# hand_fpc.net
KiCad netlist of a schematic drawn in Altium Designer
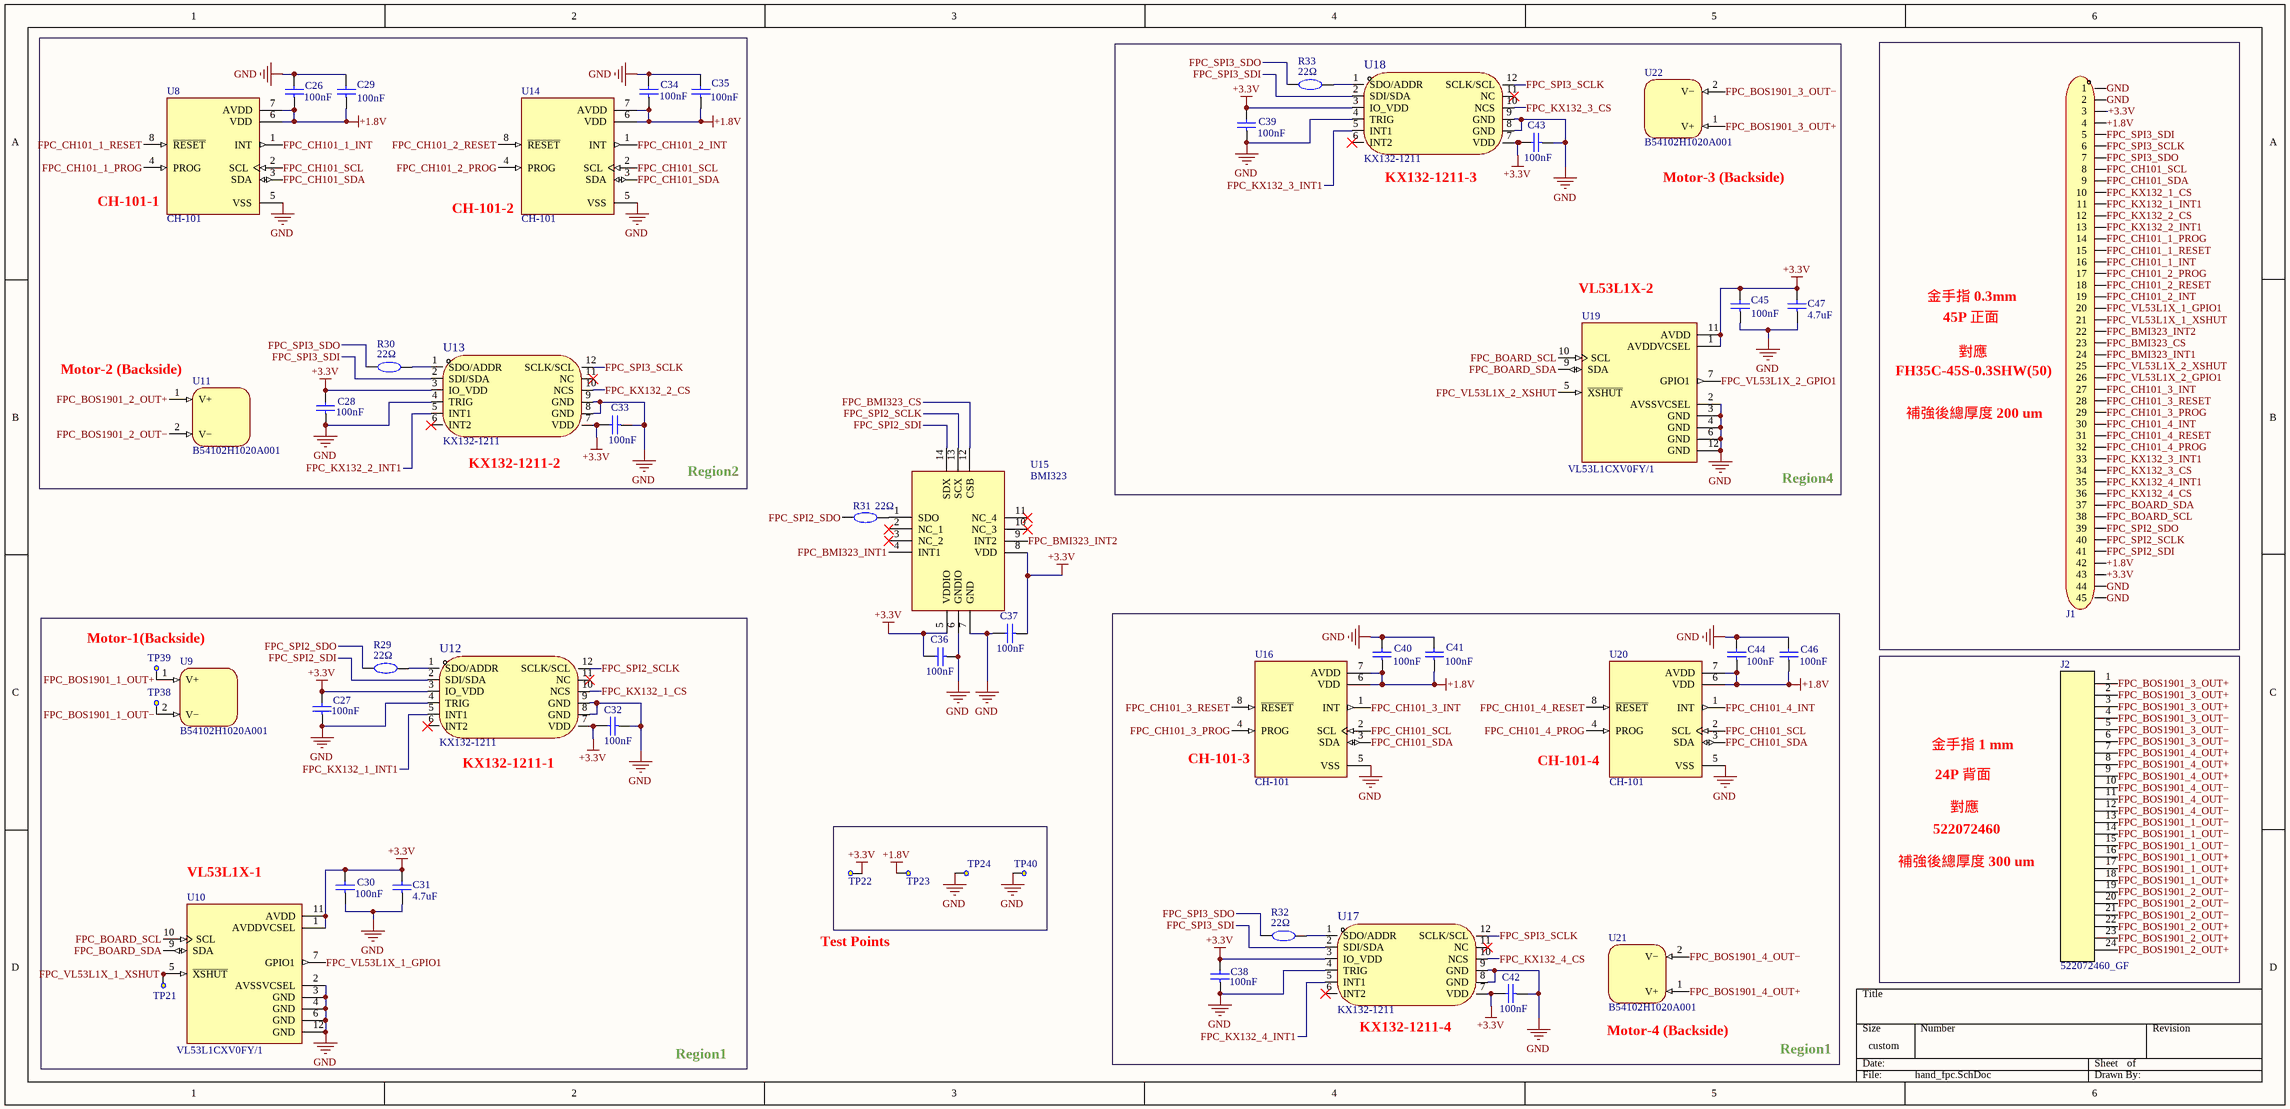
[diagram p0: hand_fpc.SchDoc]

(export (version "E")
  (design (tool "Eeschema 10.0.6"))
  (components
    (comp (ref "C26")
      (value "100nF")
      (footprint "C1206_FPC")
      (description "MLCC, 100 nF, 50 V, ± 10%, X7R, 1206")
      (fields
        (field (name "MANUFACTURER") "SAMSUNG(三星)")
        (field (name "MANUFACTURER PART") "CL31B104KBCNNNC")
      )
      (libsource (lib "hand_ad_lib") (part "CL31B104KBCNNNC"))
    )
    (comp (ref "C27")
      (value "100nF")
      (footprint "C1206_FPC")
      (description "MLCC, 100 nF, 50 V, ± 10%, X7R, 1206")
      (fields
        (field (name "MANUFACTURER") "SAMSUNG(三星)")
        (field (name "MANUFACTURER PART") "CL31B104KBCNNNC")
      )
      (libsource (lib "hand_ad_lib") (part "CL31B104KBCNNNC"))
    )
    (comp (ref "C28")
      (value "100nF")
      (footprint "C1206_FPC")
      (description "MLCC, 100 nF, 50 V, ± 10%, X7R, 1206")
      (fields
        (field (name "MANUFACTURER") "SAMSUNG(三星)")
        (field (name "MANUFACTURER PART") "CL31B104KBCNNNC")
      )
      (libsource (lib "hand_ad_lib") (part "CL31B104KBCNNNC"))
    )
    (comp (ref "C29")
      (value "100nF")
      (footprint "C1206_FPC")
      (description "MLCC, 100 nF, 50 V, ± 10%, X7R, 1206")
      (fields
        (field (name "MANUFACTURER") "SAMSUNG(三星)")
        (field (name "MANUFACTURER PART") "CL31B104KBCNNNC")
      )
      (libsource (lib "hand_ad_lib") (part "CL31B104KBCNNNC"))
    )
    (comp (ref "C30")
      (value "100nF")
      (footprint "C1206_FPC")
      (description "MLCC, 100 nF, 50 V, ± 10%, X7R, 1206")
      (fields
        (field (name "MANUFACTURER") "SAMSUNG(三星)")
        (field (name "MANUFACTURER PART") "CL31B104KBCNNNC")
      )
      (libsource (lib "hand_ad_lib") (part "CL31B104KBCNNNC"))
    )
    (comp (ref "C31")
      (value "4.7uF")
      (footprint "C1206_FPC")
      (description "MLCC, 4.7 uF, 50 V, ± 10%, X7R, 1206")
      (fields (field (name "TOLERANCE") "±10%") (field (name "MANUFACTURER") "FH(风华)"))
      (libsource (lib "hand_ad_lib") (part "1206B475K500NT"))
    )
    (comp (ref "C32")
      (value "100nF")
      (footprint "C1206_FPC")
      (description "MLCC, 100 nF, 50 V, ± 10%, X7R, 1206")
      (fields
        (field (name "MANUFACTURER") "SAMSUNG(三星)")
        (field (name "MANUFACTURER PART") "CL31B104KBCNNNC")
      )
      (libsource (lib "hand_ad_lib") (part "CL31B104KBCNNNC"))
    )
    (comp (ref "C33")
      (value "100nF")
      (footprint "C1206_FPC")
      (description "MLCC, 100 nF, 50 V, ± 10%, X7R, 1206")
      (fields
        (field (name "MANUFACTURER") "SAMSUNG(三星)")
        (field (name "MANUFACTURER PART") "CL31B104KBCNNNC")
      )
      (libsource (lib "hand_ad_lib") (part "CL31B104KBCNNNC"))
    )
    (comp (ref "C34")
      (value "100nF")
      (footprint "C1206_FPC")
      (description "MLCC, 100 nF, 50 V, ± 10%, X7R, 1206")
      (fields
        (field (name "MANUFACTURER") "SAMSUNG(三星)")
        (field (name "MANUFACTURER PART") "CL31B104KBCNNNC")
      )
      (libsource (lib "hand_ad_lib") (part "CL31B104KBCNNNC"))
    )
    (comp (ref "C35")
      (value "100nF")
      (footprint "C1206_FPC")
      (description "MLCC, 100 nF, 50 V, ± 10%, X7R, 1206")
      (fields
        (field (name "MANUFACTURER") "SAMSUNG(三星)")
        (field (name "MANUFACTURER PART") "CL31B104KBCNNNC")
      )
      (libsource (lib "hand_ad_lib") (part "CL31B104KBCNNNC"))
    )
    (comp (ref "C36")
      (value "100nF")
      (footprint "C1206_FPC")
      (description "MLCC, 100 nF, 50 V, ± 10%, X7R, 1206")
      (fields
        (field (name "MANUFACTURER") "SAMSUNG(三星)")
        (field (name "MANUFACTURER PART") "CL31B104KBCNNNC")
      )
      (libsource (lib "hand_ad_lib") (part "CL31B104KBCNNNC"))
    )
    (comp (ref "C37")
      (value "100nF")
      (footprint "C1206_FPC")
      (description "MLCC, 100 nF, 50 V, ± 10%, X7R, 1206")
      (fields
        (field (name "MANUFACTURER") "SAMSUNG(三星)")
        (field (name "MANUFACTURER PART") "CL31B104KBCNNNC")
      )
      (libsource (lib "hand_ad_lib") (part "CL31B104KBCNNNC"))
    )
    (comp (ref "C38")
      (value "100nF")
      (footprint "C1206_FPC")
      (description "MLCC, 100 nF, 50 V, ± 10%, X7R, 1206")
      (fields
        (field (name "MANUFACTURER") "SAMSUNG(三星)")
        (field (name "MANUFACTURER PART") "CL31B104KBCNNNC")
      )
      (libsource (lib "hand_ad_lib") (part "CL31B104KBCNNNC"))
    )
    (comp (ref "C39")
      (value "100nF")
      (footprint "C1206_FPC")
      (description "MLCC, 100 nF, 50 V, ± 10%, X7R, 1206")
      (fields
        (field (name "MANUFACTURER") "SAMSUNG(三星)")
        (field (name "MANUFACTURER PART") "CL31B104KBCNNNC")
      )
      (libsource (lib "hand_ad_lib") (part "CL31B104KBCNNNC"))
    )
    (comp (ref "C40")
      (value "100nF")
      (footprint "C1206_FPC")
      (description "MLCC, 100 nF, 50 V, ± 10%, X7R, 1206")
      (fields
        (field (name "MANUFACTURER") "SAMSUNG(三星)")
        (field (name "MANUFACTURER PART") "CL31B104KBCNNNC")
      )
      (libsource (lib "hand_ad_lib") (part "CL31B104KBCNNNC"))
    )
    (comp (ref "C41")
      (value "100nF")
      (footprint "C1206_FPC")
      (description "MLCC, 100 nF, 50 V, ± 10%, X7R, 1206")
      (fields
        (field (name "MANUFACTURER") "SAMSUNG(三星)")
        (field (name "MANUFACTURER PART") "CL31B104KBCNNNC")
      )
      (libsource (lib "hand_ad_lib") (part "CL31B104KBCNNNC"))
    )
    (comp (ref "C42")
      (value "100nF")
      (footprint "C1206_FPC")
      (description "MLCC, 100 nF, 50 V, ± 10%, X7R, 1206")
      (fields
        (field (name "MANUFACTURER") "SAMSUNG(三星)")
        (field (name "MANUFACTURER PART") "CL31B104KBCNNNC")
      )
      (libsource (lib "hand_ad_lib") (part "CL31B104KBCNNNC"))
    )
    (comp (ref "C43")
      (value "100nF")
      (footprint "C1206_FPC")
      (description "MLCC, 100 nF, 50 V, ± 10%, X7R, 1206")
      (fields
        (field (name "MANUFACTURER") "SAMSUNG(三星)")
        (field (name "MANUFACTURER PART") "CL31B104KBCNNNC")
      )
      (libsource (lib "hand_ad_lib") (part "CL31B104KBCNNNC"))
    )
    (comp (ref "C44")
      (value "100nF")
      (footprint "C1206_FPC")
      (description "MLCC, 100 nF, 50 V, ± 10%, X7R, 1206")
      (fields
        (field (name "MANUFACTURER") "SAMSUNG(三星)")
        (field (name "MANUFACTURER PART") "CL31B104KBCNNNC")
      )
      (libsource (lib "hand_ad_lib") (part "CL31B104KBCNNNC"))
    )
    (comp (ref "C45")
      (value "100nF")
      (footprint "C1206_FPC")
      (description "MLCC, 100 nF, 50 V, ± 10%, X7R, 1206")
      (fields
        (field (name "MANUFACTURER") "SAMSUNG(三星)")
        (field (name "MANUFACTURER PART") "CL31B104KBCNNNC")
      )
      (libsource (lib "hand_ad_lib") (part "CL31B104KBCNNNC"))
    )
    (comp (ref "C46")
      (value "100nF")
      (footprint "C1206_FPC")
      (description "MLCC, 100 nF, 50 V, ± 10%, X7R, 1206")
      (fields
        (field (name "MANUFACTURER") "SAMSUNG(三星)")
        (field (name "MANUFACTURER PART") "CL31B104KBCNNNC")
      )
      (libsource (lib "hand_ad_lib") (part "CL31B104KBCNNNC"))
    )
    (comp (ref "C47")
      (value "4.7uF")
      (footprint "C1206_FPC")
      (description "MLCC, 4.7 uF, 50 V, ± 10%, X7R, 1206")
      (fields (field (name "TOLERANCE") "±10%") (field (name "MANUFACTURER") "FH(风华)"))
      (libsource (lib "hand_ad_lib") (part "1206B475K500NT"))
    )
    (comp (ref "J1")
      (value "FH35C-45S-0.3SHW-GF")
      (footprint "FH35C-45S-0.3SHW-GF-REVERSE")
      (description "Golden Finger Footprint of FH35C-45S-0.3SHW, 45 Pins, 0.3mm cross, up contact")
      (libsource (lib "hand_ad_lib") (part "FH35C-45S-0.3SHW-GF"))
    )
    (comp (ref "J2")
      (value "522072460_GF")
      (footprint "522072460-GF-Back")
      (description "FFC 1mm 24P Golden Finger")
      (libsource (lib "hand_ad_lib") (part "522072460_GF"))
    )
    (comp (ref "R29")
      (value "22Ω")
      (footprint "R1206_FPC")
      (description "Resistor, Res Thick Film 1206 22 Ohm 1% 0.25W(1/4W) ±100ppm/°C Pad SMD T/R 200 V")
      (fields
        (field (name "MANUFACTURER") "UNI-ROYAL(厚声)")
        (field (name "MANUFACTURER PART") "1206W4F220JT5E")
        (field (name "NAME") "22Ω")
      )
      (libsource (lib "hand_ad_lib") (part "1206W4F220JT5E"))
    )
    (comp (ref "R30")
      (value "22Ω")
      (footprint "R1206_FPC")
      (description "Resistor, Res Thick Film 1206 22 Ohm 1% 0.25W(1/4W) ±100ppm/°C Pad SMD T/R 200 V")
      (fields
        (field (name "MANUFACTURER") "UNI-ROYAL(厚声)")
        (field (name "MANUFACTURER PART") "1206W4F220JT5E")
        (field (name "NAME") "22Ω")
      )
      (libsource (lib "hand_ad_lib") (part "1206W4F220JT5E"))
    )
    (comp (ref "R31")
      (value "22Ω")
      (footprint "R1206_FPC")
      (description "Resistor, Res Thick Film 1206 22 Ohm 1% 0.25W(1/4W) ±100ppm/°C Pad SMD T/R 200 V")
      (fields
        (field (name "MANUFACTURER") "UNI-ROYAL(厚声)")
        (field (name "MANUFACTURER PART") "1206W4F220JT5E")
        (field (name "NAME") "22Ω")
      )
      (libsource (lib "hand_ad_lib") (part "1206W4F220JT5E"))
    )
    (comp (ref "R32")
      (value "22Ω")
      (footprint "R1206_FPC")
      (description "Resistor, Res Thick Film 1206 22 Ohm 1% 0.25W(1/4W) ±100ppm/°C Pad SMD T/R 200 V")
      (fields
        (field (name "MANUFACTURER") "UNI-ROYAL(厚声)")
        (field (name "MANUFACTURER PART") "1206W4F220JT5E")
        (field (name "NAME") "22Ω")
      )
      (libsource (lib "hand_ad_lib") (part "1206W4F220JT5E"))
    )
    (comp (ref "R33")
      (value "22Ω")
      (footprint "R1206_FPC")
      (description "Resistor, Res Thick Film 1206 22 Ohm 1% 0.25W(1/4W) ±100ppm/°C Pad SMD T/R 200 V")
      (fields
        (field (name "MANUFACTURER") "UNI-ROYAL(厚声)")
        (field (name "MANUFACTURER PART") "1206W4F220JT5E")
        (field (name "NAME") "22Ω")
      )
      (libsource (lib "hand_ad_lib") (part "1206W4F220JT5E"))
    )
    (comp (ref "TP21")
      (value "Test point")
      (footprint "Test_Point_FPC")
      (libsource (lib "hand_ad_lib") (part "Test_Point"))
    )
    (comp (ref "TP22")
      (value "Test point")
      (footprint "Test_Point_FPC")
      (libsource (lib "hand_ad_lib") (part "Test_Point"))
    )
    (comp (ref "TP23")
      (value "Test point")
      (footprint "Test_Point_FPC")
      (libsource (lib "hand_ad_lib") (part "Test_Point"))
    )
    (comp (ref "TP24")
      (value "Test point")
      (footprint "Test_Point_FPC")
      (libsource (lib "hand_ad_lib") (part "Test_Point"))
    )
    (comp (ref "TP38")
      (value "Test point")
      (footprint "Test_Point_FPC")
      (libsource (lib "hand_ad_lib") (part "Test_Point"))
    )
    (comp (ref "TP39")
      (value "Test point")
      (footprint "Test_Point_FPC")
      (libsource (lib "hand_ad_lib") (part "Test_Point"))
    )
    (comp (ref "TP40")
      (value "Test point")
      (footprint "Test_Point_FPC")
      (libsource (lib "hand_ad_lib") (part "Test_Point"))
    )
    (comp (ref "U8")
      (value "CH-101")
      (footprint "XDCR_CH-101")
      (description "Ultrasonic MEMS based Time-of-Flight _ToF_ Range Sensor")
      (fields (field (name "MF") "TDK InvenSense"))
      (libsource (lib "hand_ad_lib") (part "CH-101"))
    )
    (comp (ref "U9")
      (value "B54102H1020A001")
      (footprint "B54102H1020A001")
      (description "TDK PowerHap™, Piezo Haptic Actuator Metal Sealed 15N 65um 32KHz Bulk")
      (fields (field (name "MANUFACTURER") "TDK EPCOS") (field (name "NAME") "B54102H1020A001"))
      (libsource (lib "hand_ad_lib") (part "B54102H1020A001"))
    )
    (comp (ref "U10")
      (value "VL53L1CXV0FY/1")
      (footprint "SENSOR_VL53L1CXV0FY/1")
      (description "Optical Sensor 157.480 (4m) I2C Output")
      (fields (field (name "MF") "STMicroelectronics"))
      (libsource (lib "hand_ad_lib") (part "VL53L1CXV0FY/1"))
    )
    (comp (ref "U11")
      (value "B54102H1020A001")
      (footprint "B54102H1020A001")
      (description "TDK PowerHap™, Piezo Haptic Actuator Metal Sealed 15N 65um 32KHz Bulk")
      (fields (field (name "MANUFACTURER") "TDK EPCOS") (field (name "NAME") "B54102H1020A001"))
      (libsource (lib "hand_ad_lib") (part "B54102H1020A001"))
    )
    (comp (ref "U12")
      (value "KX132-1211")
      (footprint "LGA-12_L2.0-W2.0-P0.50-TL")
      (description "KX132 Series 3.6 V ±2g/4g/8g/16g SMT 3 Axis Digital Accelerometer- LGA-12")
      (fields (field (name "MANUFACTURER") "ROHM(罗姆)") (field (name "NAME") "KX132-1211"))
      (libsource (lib "hand_ad_lib") (part "KX132-1211"))
    )
    (comp (ref "U13")
      (value "KX132-1211")
      (footprint "LGA-12_L2.0-W2.0-P0.50-TL")
      (description "KX132 Series 3.6 V ±2g/4g/8g/16g SMT 3 Axis Digital Accelerometer- LGA-12")
      (fields (field (name "MANUFACTURER") "ROHM(罗姆)") (field (name "NAME") "KX132-1211"))
      (libsource (lib "hand_ad_lib") (part "KX132-1211"))
    )
    (comp (ref "U14")
      (value "CH-101")
      (footprint "XDCR_CH-101")
      (description "Ultrasonic MEMS based Time-of-Flight _ToF_ Range Sensor")
      (fields (field (name "MF") "TDK InvenSense"))
      (libsource (lib "hand_ad_lib") (part "CH-101"))
    )
    (comp (ref "U15")
      (value "BMI323")
      (footprint "BMI323")
      (description "BOSCH IMU IC")
      (fields (field (name "MOUSER PART NUMBER") "262-BMI323"))
      (libsource (lib "hand_ad_lib") (part "BMI323"))
    )
    (comp (ref "U16")
      (value "CH-101")
      (footprint "XDCR_CH-101")
      (description "Ultrasonic MEMS based Time-of-Flight _ToF_ Range Sensor")
      (fields (field (name "MF") "TDK InvenSense"))
      (libsource (lib "hand_ad_lib") (part "CH-101"))
    )
    (comp (ref "U17")
      (value "KX132-1211")
      (footprint "LGA-12_L2.0-W2.0-P0.50-TL")
      (description "KX132 Series 3.6 V ±2g/4g/8g/16g SMT 3 Axis Digital Accelerometer- LGA-12")
      (fields (field (name "MANUFACTURER") "ROHM(罗姆)") (field (name "NAME") "KX132-1211"))
      (libsource (lib "hand_ad_lib") (part "KX132-1211"))
    )
    (comp (ref "U18")
      (value "KX132-1211")
      (footprint "LGA-12_L2.0-W2.0-P0.50-TL")
      (description "KX132 Series 3.6 V ±2g/4g/8g/16g SMT 3 Axis Digital Accelerometer- LGA-12")
      (fields (field (name "MANUFACTURER") "ROHM(罗姆)") (field (name "NAME") "KX132-1211"))
      (libsource (lib "hand_ad_lib") (part "KX132-1211"))
    )
    (comp (ref "U19")
      (value "VL53L1CXV0FY/1")
      (footprint "SENSOR_VL53L1CXV0FY/1")
      (description "Optical Sensor 157.480 (4m) I2C Output")
      (fields (field (name "MF") "STMicroelectronics"))
      (libsource (lib "hand_ad_lib") (part "VL53L1CXV0FY/1"))
    )
    (comp (ref "U20")
      (value "CH-101")
      (footprint "XDCR_CH-101")
      (description "Ultrasonic MEMS based Time-of-Flight _ToF_ Range Sensor")
      (fields (field (name "MF") "TDK InvenSense"))
      (libsource (lib "hand_ad_lib") (part "CH-101"))
    )
    (comp (ref "U21")
      (value "B54102H1020A001")
      (footprint "B54102H1020A001")
      (description "TDK PowerHap™, Piezo Haptic Actuator Metal Sealed 15N 65um 32KHz Bulk")
      (fields (field (name "MANUFACTURER") "TDK EPCOS") (field (name "NAME") "B54102H1020A001"))
      (libsource (lib "hand_ad_lib") (part "B54102H1020A001"))
    )
    (comp (ref "U22")
      (value "B54102H1020A001")
      (footprint "B54102H1020A001")
      (description "TDK PowerHap™, Piezo Haptic Actuator Metal Sealed 15N 65um 32KHz Bulk")
      (fields (field (name "MANUFACTURER") "TDK EPCOS") (field (name "NAME") "B54102H1020A001"))
      (libsource (lib "hand_ad_lib") (part "B54102H1020A001"))
    )
  )
  (nets
    (net (code "1") (name "+1.8V") (class "Default")
      (node (ref "C26") (pin "1") (pinfunction "1_1") (pintype "passive"))
      (node (ref "C29") (pin "1") (pinfunction "1_1") (pintype "passive"))
      (node (ref "C34") (pin "1") (pinfunction "1_1") (pintype "passive"))
      (node (ref "C35") (pin "1") (pinfunction "1_1") (pintype "passive"))
      (node (ref "C40") (pin "1") (pinfunction "1_1") (pintype "passive"))
      (node (ref "C41") (pin "1") (pinfunction "1_1") (pintype "passive"))
      (node (ref "C44") (pin "1") (pinfunction "1_1") (pintype "passive"))
      (node (ref "C46") (pin "1") (pinfunction "1_1") (pintype "passive"))
      (node (ref "J1") (pin "4") (pinfunction "4_4") (pintype "passive"))
      (node (ref "J1") (pin "42") (pinfunction "42_42") (pintype "passive"))
      (node (ref "TP23") (pin "TP?") (pinfunction "Test_point_TP?") (pintype "passive"))
      (node (ref "U14") (pin "6") (pinfunction "VDD_6") (pintype "power_in"))
      (node (ref "U14") (pin "7") (pinfunction "AVDD_7") (pintype "power_in"))
      (node (ref "U16") (pin "6") (pinfunction "VDD_6") (pintype "power_in"))
      (node (ref "U16") (pin "7") (pinfunction "AVDD_7") (pintype "power_in"))
      (node (ref "U20") (pin "6") (pinfunction "VDD_6") (pintype "power_in"))
      (node (ref "U20") (pin "7") (pinfunction "AVDD_7") (pintype "power_in"))
      (node (ref "U8") (pin "6") (pinfunction "VDD_6") (pintype "power_in"))
      (node (ref "U8") (pin "7") (pinfunction "AVDD_7") (pintype "power_in"))
    )
    (net (code "2") (name "+3.3V") (class "Default")
      (node (ref "C27") (pin "2") (pinfunction "2_2") (pintype "passive"))
      (node (ref "C28") (pin "2") (pinfunction "2_2") (pintype "passive"))
      (node (ref "C30") (pin "2") (pinfunction "2_2") (pintype "passive"))
      (node (ref "C31") (pin "2") (pinfunction "2_2") (pintype "passive"))
      (node (ref "C32") (pin "2") (pinfunction "2_2") (pintype "passive"))
      (node (ref "C33") (pin "2") (pinfunction "2_2") (pintype "passive"))
      (node (ref "C36") (pin "2") (pinfunction "2_2") (pintype "passive"))
      (node (ref "C37") (pin "1") (pinfunction "1_1") (pintype "passive"))
      (node (ref "C38") (pin "2") (pinfunction "2_2") (pintype "passive"))
      (node (ref "C39") (pin "2") (pinfunction "2_2") (pintype "passive"))
      (node (ref "C42") (pin "2") (pinfunction "2_2") (pintype "passive"))
      (node (ref "C43") (pin "2") (pinfunction "2_2") (pintype "passive"))
      (node (ref "C45") (pin "2") (pinfunction "2_2") (pintype "passive"))
      (node (ref "C47") (pin "2") (pinfunction "2_2") (pintype "passive"))
      (node (ref "J1") (pin "3") (pinfunction "3_3") (pintype "passive"))
      (node (ref "J1") (pin "43") (pinfunction "43_43") (pintype "passive"))
      (node (ref "TP22") (pin "TP?") (pinfunction "Test_point_TP?") (pintype "passive"))
      (node (ref "U10") (pin "1") (pinfunction "AVDDVCSEL_1") (pintype "power_in"))
      (node (ref "U10") (pin "11") (pinfunction "AVDD_11") (pintype "power_in"))
      (node (ref "U12") (pin "3") (pinfunction "IO_VDD_3") (pintype "passive"))
      (node (ref "U12") (pin "7") (pinfunction "VDD_7") (pintype "passive"))
      (node (ref "U13") (pin "3") (pinfunction "IO_VDD_3") (pintype "passive"))
      (node (ref "U13") (pin "7") (pinfunction "VDD_7") (pintype "passive"))
      (node (ref "U15") (pin "5") (pinfunction "VDDIO_5") (pintype "passive"))
      (node (ref "U15") (pin "8") (pinfunction "VDD_8") (pintype "passive"))
      (node (ref "U17") (pin "3") (pinfunction "IO_VDD_3") (pintype "passive"))
      (node (ref "U17") (pin "7") (pinfunction "VDD_7") (pintype "passive"))
      (node (ref "U18") (pin "3") (pinfunction "IO_VDD_3") (pintype "passive"))
      (node (ref "U18") (pin "7") (pinfunction "VDD_7") (pintype "passive"))
      (node (ref "U19") (pin "1") (pinfunction "AVDDVCSEL_1") (pintype "power_in"))
      (node (ref "U19") (pin "11") (pinfunction "AVDD_11") (pintype "power_in"))
    )
    (net (code "3") (name "/FPC_BMI323_CS") (class "Default")
      (node (ref "J1") (pin "23") (pinfunction "23_23") (pintype "passive"))
      (node (ref "U15") (pin "12") (pinfunction "CSB_12") (pintype "passive"))
    )
    (net (code "4") (name "/FPC_BMI323_INT1") (class "Default")
      (node (ref "J1") (pin "24") (pinfunction "24_24") (pintype "passive"))
      (node (ref "U15") (pin "4") (pinfunction "INT1_4") (pintype "passive"))
    )
    (net (code "5") (name "/FPC_BMI323_INT2") (class "Default")
      (node (ref "J1") (pin "22") (pinfunction "22_22") (pintype "passive"))
      (node (ref "U15") (pin "9") (pinfunction "INT2_9") (pintype "passive"))
    )
    (net (code "6") (name "/FPC_BOARD_SCL") (class "Default")
      (node (ref "J1") (pin "38") (pinfunction "38_38") (pintype "passive"))
      (node (ref "U10") (pin "10") (pinfunction "SCL_10") (pintype "input"))
      (node (ref "U19") (pin "10") (pinfunction "SCL_10") (pintype "input"))
    )
    (net (code "7") (name "/FPC_BOARD_SDA") (class "Default")
      (node (ref "J1") (pin "37") (pinfunction "37_37") (pintype "passive"))
      (node (ref "U10") (pin "9") (pinfunction "SDA_9") (pintype "bidirectional"))
      (node (ref "U19") (pin "9") (pinfunction "SDA_9") (pintype "bidirectional"))
    )
    (net (code "8") (name "/FPC_BOS1901_1_OUT+") (class "Default")
      (node (ref "J2") (pin "16") (pinfunction "16_16") (pintype "passive"))
      (node (ref "J2") (pin "17") (pinfunction "17_17") (pintype "passive"))
      (node (ref "J2") (pin "18") (pinfunction "18_18") (pintype "passive"))
      (node (ref "TP39") (pin "TP?") (pinfunction "Test_point_TP?") (pintype "passive"))
      (node (ref "U9") (pin "1") (pinfunction "V+_1") (pintype "input"))
    )
    (net (code "9") (name "/FPC_BOS1901_1_OUT−") (class "Default")
      (node (ref "J2") (pin "13") (pinfunction "13_13") (pintype "passive"))
      (node (ref "J2") (pin "14") (pinfunction "14_14") (pintype "passive"))
      (node (ref "J2") (pin "15") (pinfunction "15_15") (pintype "passive"))
      (node (ref "TP38") (pin "TP?") (pinfunction "Test_point_TP?") (pintype "passive"))
      (node (ref "U9") (pin "2") (pinfunction "V−_2") (pintype "input"))
    )
    (net (code "10") (name "/FPC_BOS1901_2_OUT+") (class "Default")
      (node (ref "J2") (pin "22") (pinfunction "22_22") (pintype "passive"))
      (node (ref "J2") (pin "23") (pinfunction "23_23") (pintype "passive"))
      (node (ref "J2") (pin "24") (pinfunction "24_24") (pintype "passive"))
      (node (ref "U11") (pin "1") (pinfunction "V+_1") (pintype "input"))
    )
    (net (code "11") (name "/FPC_BOS1901_2_OUT−") (class "Default")
      (node (ref "J2") (pin "19") (pinfunction "19_19") (pintype "passive"))
      (node (ref "J2") (pin "20") (pinfunction "20_20") (pintype "passive"))
      (node (ref "J2") (pin "21") (pinfunction "21_21") (pintype "passive"))
      (node (ref "U11") (pin "2") (pinfunction "V−_2") (pintype "input"))
    )
    (net (code "12") (name "/FPC_BOS1901_3_OUT+") (class "Default")
      (node (ref "J2") (pin "1") (pinfunction "1_1") (pintype "passive"))
      (node (ref "J2") (pin "2") (pinfunction "2_2") (pintype "passive"))
      (node (ref "J2") (pin "3") (pinfunction "3_3") (pintype "passive"))
      (node (ref "U22") (pin "1") (pinfunction "V+_1") (pintype "input"))
    )
    (net (code "13") (name "/FPC_BOS1901_3_OUT−") (class "Default")
      (node (ref "J2") (pin "4") (pinfunction "4_4") (pintype "passive"))
      (node (ref "J2") (pin "5") (pinfunction "5_5") (pintype "passive"))
      (node (ref "J2") (pin "6") (pinfunction "6_6") (pintype "passive"))
      (node (ref "U22") (pin "2") (pinfunction "V−_2") (pintype "input"))
    )
    (net (code "14") (name "/FPC_BOS1901_4_OUT+") (class "Default")
      (node (ref "J2") (pin "7") (pinfunction "7_7") (pintype "passive"))
      (node (ref "J2") (pin "8") (pinfunction "8_8") (pintype "passive"))
      (node (ref "J2") (pin "9") (pinfunction "9_9") (pintype "passive"))
      (node (ref "U21") (pin "1") (pinfunction "V+_1") (pintype "input"))
    )
    (net (code "15") (name "/FPC_BOS1901_4_OUT−") (class "Default")
      (node (ref "J2") (pin "10") (pinfunction "10_10") (pintype "passive"))
      (node (ref "J2") (pin "11") (pinfunction "11_11") (pintype "passive"))
      (node (ref "J2") (pin "12") (pinfunction "12_12") (pintype "passive"))
      (node (ref "U21") (pin "2") (pinfunction "V−_2") (pintype "input"))
    )
    (net (code "16") (name "/FPC_CH101_1_INT") (class "Default")
      (node (ref "J1") (pin "16") (pinfunction "16_16") (pintype "passive"))
      (node (ref "U8") (pin "1") (pinfunction "INT_1") (pintype "output"))
    )
    (net (code "17") (name "/FPC_CH101_1_PROG") (class "Default")
      (node (ref "J1") (pin "14") (pinfunction "14_14") (pintype "passive"))
      (node (ref "U8") (pin "4") (pinfunction "PROG_4") (pintype "input"))
    )
    (net (code "18") (name "/FPC_CH101_1_RESET") (class "Default")
      (node (ref "J1") (pin "15") (pinfunction "15_15") (pintype "passive"))
      (node (ref "U8") (pin "8") (pinfunction "~{RESET}_8") (pintype "input"))
    )
    (net (code "19") (name "/FPC_CH101_2_INT") (class "Default")
      (node (ref "J1") (pin "19") (pinfunction "19_19") (pintype "passive"))
      (node (ref "U14") (pin "1") (pinfunction "INT_1") (pintype "output"))
    )
    (net (code "20") (name "/FPC_CH101_2_PROG") (class "Default")
      (node (ref "J1") (pin "17") (pinfunction "17_17") (pintype "passive"))
      (node (ref "U14") (pin "4") (pinfunction "PROG_4") (pintype "input"))
    )
    (net (code "21") (name "/FPC_CH101_2_RESET") (class "Default")
      (node (ref "J1") (pin "18") (pinfunction "18_18") (pintype "passive"))
      (node (ref "U14") (pin "8") (pinfunction "~{RESET}_8") (pintype "input"))
    )
    (net (code "22") (name "/FPC_CH101_3_INT") (class "Default")
      (node (ref "J1") (pin "27") (pinfunction "27_27") (pintype "passive"))
      (node (ref "U16") (pin "1") (pinfunction "INT_1") (pintype "output"))
    )
    (net (code "23") (name "/FPC_CH101_3_PROG") (class "Default")
      (node (ref "J1") (pin "29") (pinfunction "29_29") (pintype "passive"))
      (node (ref "U16") (pin "4") (pinfunction "PROG_4") (pintype "input"))
    )
    (net (code "24") (name "/FPC_CH101_3_RESET") (class "Default")
      (node (ref "J1") (pin "28") (pinfunction "28_28") (pintype "passive"))
      (node (ref "U16") (pin "8") (pinfunction "~{RESET}_8") (pintype "input"))
    )
    (net (code "25") (name "/FPC_CH101_4_INT") (class "Default")
      (node (ref "J1") (pin "30") (pinfunction "30_30") (pintype "passive"))
      (node (ref "U20") (pin "1") (pinfunction "INT_1") (pintype "output"))
    )
    (net (code "26") (name "/FPC_CH101_4_PROG") (class "Default")
      (node (ref "J1") (pin "32") (pinfunction "32_32") (pintype "passive"))
      (node (ref "U20") (pin "4") (pinfunction "PROG_4") (pintype "input"))
    )
    (net (code "27") (name "/FPC_CH101_4_RESET") (class "Default")
      (node (ref "J1") (pin "31") (pinfunction "31_31") (pintype "passive"))
      (node (ref "U20") (pin "8") (pinfunction "~{RESET}_8") (pintype "input"))
    )
    (net (code "28") (name "/FPC_CH101_SCL") (class "Default")
      (node (ref "J1") (pin "8") (pinfunction "8_8") (pintype "passive"))
      (node (ref "U14") (pin "2") (pinfunction "SCL_2") (pintype "input"))
      (node (ref "U16") (pin "2") (pinfunction "SCL_2") (pintype "input"))
      (node (ref "U20") (pin "2") (pinfunction "SCL_2") (pintype "input"))
      (node (ref "U8") (pin "2") (pinfunction "SCL_2") (pintype "input"))
    )
    (net (code "29") (name "/FPC_CH101_SDA") (class "Default")
      (node (ref "J1") (pin "9") (pinfunction "9_9") (pintype "passive"))
      (node (ref "U14") (pin "3") (pinfunction "SDA_3") (pintype "bidirectional"))
      (node (ref "U16") (pin "3") (pinfunction "SDA_3") (pintype "bidirectional"))
      (node (ref "U20") (pin "3") (pinfunction "SDA_3") (pintype "bidirectional"))
      (node (ref "U8") (pin "3") (pinfunction "SDA_3") (pintype "bidirectional"))
    )
    (net (code "30") (name "/FPC_KX132_1_CS") (class "Default")
      (node (ref "J1") (pin "10") (pinfunction "10_10") (pintype "passive"))
      (node (ref "U12") (pin "10") (pinfunction "NCS_10") (pintype "passive"))
    )
    (net (code "31") (name "/FPC_KX132_1_INT1") (class "Default")
      (node (ref "J1") (pin "11") (pinfunction "11_11") (pintype "passive"))
      (node (ref "U12") (pin "5") (pinfunction "INT1_5") (pintype "passive"))
    )
    (net (code "32") (name "/FPC_KX132_2_CS") (class "Default")
      (node (ref "J1") (pin "12") (pinfunction "12_12") (pintype "passive"))
      (node (ref "U13") (pin "10") (pinfunction "NCS_10") (pintype "passive"))
    )
    (net (code "33") (name "/FPC_KX132_2_INT1") (class "Default")
      (node (ref "J1") (pin "13") (pinfunction "13_13") (pintype "passive"))
      (node (ref "U13") (pin "5") (pinfunction "INT1_5") (pintype "passive"))
    )
    (net (code "34") (name "/FPC_KX132_3_CS") (class "Default")
      (node (ref "J1") (pin "34") (pinfunction "34_34") (pintype "passive"))
      (node (ref "U18") (pin "10") (pinfunction "NCS_10") (pintype "passive"))
    )
    (net (code "35") (name "/FPC_KX132_3_INT1") (class "Default")
      (node (ref "J1") (pin "33") (pinfunction "33_33") (pintype "passive"))
      (node (ref "U18") (pin "5") (pinfunction "INT1_5") (pintype "passive"))
    )
    (net (code "36") (name "/FPC_KX132_4_CS") (class "Default")
      (node (ref "J1") (pin "36") (pinfunction "36_36") (pintype "passive"))
      (node (ref "U17") (pin "10") (pinfunction "NCS_10") (pintype "passive"))
    )
    (net (code "37") (name "/FPC_KX132_4_INT1") (class "Default")
      (node (ref "J1") (pin "35") (pinfunction "35_35") (pintype "passive"))
      (node (ref "U17") (pin "5") (pinfunction "INT1_5") (pintype "passive"))
    )
    (net (code "38") (name "/FPC_SPI2_SCLK") (class "Default")
      (node (ref "J1") (pin "40") (pinfunction "40_40") (pintype "passive"))
      (node (ref "U12") (pin "12") (pinfunction "SCLK/SCL_12") (pintype "passive"))
      (node (ref "U15") (pin "13") (pinfunction "SCX_13") (pintype "passive"))
    )
    (net (code "39") (name "/FPC_SPI2_SDI") (class "Default")
      (node (ref "J1") (pin "41") (pinfunction "41_41") (pintype "passive"))
      (node (ref "U12") (pin "2") (pinfunction "SDI/SDA_2") (pintype "passive"))
      (node (ref "U15") (pin "14") (pinfunction "SDX_14") (pintype "passive"))
    )
    (net (code "40") (name "/FPC_SPI2_SDO") (class "Default")
      (node (ref "J1") (pin "39") (pinfunction "39_39") (pintype "passive"))
      (node (ref "R29") (pin "1") (pinfunction "1_1") (pintype "passive"))
      (node (ref "R31") (pin "1") (pinfunction "1_1") (pintype "passive"))
    )
    (net (code "41") (name "/FPC_SPI3_SCLK") (class "Default")
      (node (ref "J1") (pin "6") (pinfunction "6_6") (pintype "passive"))
      (node (ref "U13") (pin "12") (pinfunction "SCLK/SCL_12") (pintype "passive"))
      (node (ref "U17") (pin "12") (pinfunction "SCLK/SCL_12") (pintype "passive"))
      (node (ref "U18") (pin "12") (pinfunction "SCLK/SCL_12") (pintype "passive"))
    )
    (net (code "42") (name "/FPC_SPI3_SDI") (class "Default")
      (node (ref "J1") (pin "5") (pinfunction "5_5") (pintype "passive"))
      (node (ref "U13") (pin "2") (pinfunction "SDI/SDA_2") (pintype "passive"))
      (node (ref "U17") (pin "2") (pinfunction "SDI/SDA_2") (pintype "passive"))
      (node (ref "U18") (pin "2") (pinfunction "SDI/SDA_2") (pintype "passive"))
    )
    (net (code "43") (name "/FPC_SPI3_SDO") (class "Default")
      (node (ref "J1") (pin "7") (pinfunction "7_7") (pintype "passive"))
      (node (ref "R30") (pin "1") (pinfunction "1_1") (pintype "passive"))
      (node (ref "R32") (pin "1") (pinfunction "1_1") (pintype "passive"))
      (node (ref "R33") (pin "1") (pinfunction "1_1") (pintype "passive"))
    )
    (net (code "44") (name "/FPC_VL53L1X_1_GPIO1") (class "Default")
      (node (ref "J1") (pin "20") (pinfunction "20_20") (pintype "passive"))
      (node (ref "U10") (pin "7") (pinfunction "GPIO1_7") (pintype "output"))
    )
    (net (code "45") (name "/FPC_VL53L1X_1_XSHUT") (class "Default")
      (node (ref "J1") (pin "21") (pinfunction "21_21") (pintype "passive"))
      (node (ref "TP21") (pin "TP?") (pinfunction "Test_point_TP?") (pintype "passive"))
      (node (ref "U10") (pin "5") (pinfunction "~{XSHUT}_5") (pintype "input"))
    )
    (net (code "46") (name "/FPC_VL53L1X_2_GPIO1") (class "Default")
      (node (ref "J1") (pin "26") (pinfunction "26_26") (pintype "passive"))
      (node (ref "U19") (pin "7") (pinfunction "GPIO1_7") (pintype "output"))
    )
    (net (code "47") (name "/FPC_VL53L1X_2_XSHUT") (class "Default")
      (node (ref "J1") (pin "25") (pinfunction "25_25") (pintype "passive"))
      (node (ref "U19") (pin "5") (pinfunction "~{XSHUT}_5") (pintype "input"))
    )
    (net (code "48") (name "GND") (class "Default")
      (node (ref "C26") (pin "2") (pinfunction "2_2") (pintype "passive"))
      (node (ref "C27") (pin "1") (pinfunction "1_1") (pintype "passive"))
      (node (ref "C28") (pin "1") (pinfunction "1_1") (pintype "passive"))
      (node (ref "C29") (pin "2") (pinfunction "2_2") (pintype "passive"))
      (node (ref "C30") (pin "1") (pinfunction "1_1") (pintype "passive"))
      (node (ref "C31") (pin "1") (pinfunction "1_1") (pintype "passive"))
      (node (ref "C32") (pin "1") (pinfunction "1_1") (pintype "passive"))
      (node (ref "C33") (pin "1") (pinfunction "1_1") (pintype "passive"))
      (node (ref "C34") (pin "2") (pinfunction "2_2") (pintype "passive"))
      (node (ref "C35") (pin "2") (pinfunction "2_2") (pintype "passive"))
      (node (ref "C36") (pin "1") (pinfunction "1_1") (pintype "passive"))
      (node (ref "C37") (pin "2") (pinfunction "2_2") (pintype "passive"))
      (node (ref "C38") (pin "1") (pinfunction "1_1") (pintype "passive"))
      (node (ref "C39") (pin "1") (pinfunction "1_1") (pintype "passive"))
      (node (ref "C40") (pin "2") (pinfunction "2_2") (pintype "passive"))
      (node (ref "C41") (pin "2") (pinfunction "2_2") (pintype "passive"))
      (node (ref "C42") (pin "1") (pinfunction "1_1") (pintype "passive"))
      (node (ref "C43") (pin "1") (pinfunction "1_1") (pintype "passive"))
      (node (ref "C44") (pin "2") (pinfunction "2_2") (pintype "passive"))
      (node (ref "C45") (pin "1") (pinfunction "1_1") (pintype "passive"))
      (node (ref "C46") (pin "2") (pinfunction "2_2") (pintype "passive"))
      (node (ref "C47") (pin "1") (pinfunction "1_1") (pintype "passive"))
      (node (ref "J1") (pin "1") (pinfunction "1_1") (pintype "passive"))
      (node (ref "J1") (pin "2") (pinfunction "2_2") (pintype "passive"))
      (node (ref "J1") (pin "44") (pinfunction "44_44") (pintype "passive"))
      (node (ref "J1") (pin "45") (pinfunction "45_45") (pintype "passive"))
      (node (ref "TP24") (pin "TP?") (pinfunction "Test_point_TP?") (pintype "passive"))
      (node (ref "TP40") (pin "TP?") (pinfunction "Test_point_TP?") (pintype "passive"))
      (node (ref "U10") (pin "12") (pinfunction "GND_12") (pintype "power_in"))
      (node (ref "U10") (pin "2") (pinfunction "AVSSVCSEL_2") (pintype "power_in"))
      (node (ref "U10") (pin "3") (pinfunction "GND_3") (pintype "power_in"))
      (node (ref "U10") (pin "4") (pinfunction "GND_4") (pintype "power_in"))
      (node (ref "U10") (pin "6") (pinfunction "GND_6") (pintype "power_in"))
      (node (ref "U12") (pin "4") (pinfunction "TRIG_4") (pintype "passive"))
      (node (ref "U12") (pin "8") (pinfunction "GND_8") (pintype "passive"))
      (node (ref "U12") (pin "9") (pinfunction "GND_9") (pintype "passive"))
      (node (ref "U13") (pin "4") (pinfunction "TRIG_4") (pintype "passive"))
      (node (ref "U13") (pin "8") (pinfunction "GND_8") (pintype "passive"))
      (node (ref "U13") (pin "9") (pinfunction "GND_9") (pintype "passive"))
      (node (ref "U14") (pin "5") (pinfunction "VSS_5") (pintype "power_in"))
      (node (ref "U15") (pin "6") (pinfunction "GNDIO_6") (pintype "passive"))
      (node (ref "U15") (pin "7") (pinfunction "GND_7") (pintype "passive"))
      (node (ref "U16") (pin "5") (pinfunction "VSS_5") (pintype "power_in"))
      (node (ref "U17") (pin "4") (pinfunction "TRIG_4") (pintype "passive"))
      (node (ref "U17") (pin "8") (pinfunction "GND_8") (pintype "passive"))
      (node (ref "U17") (pin "9") (pinfunction "GND_9") (pintype "passive"))
      (node (ref "U18") (pin "4") (pinfunction "TRIG_4") (pintype "passive"))
      (node (ref "U18") (pin "8") (pinfunction "GND_8") (pintype "passive"))
      (node (ref "U18") (pin "9") (pinfunction "GND_9") (pintype "passive"))
      (node (ref "U19") (pin "12") (pinfunction "GND_12") (pintype "power_in"))
      (node (ref "U19") (pin "2") (pinfunction "AVSSVCSEL_2") (pintype "power_in"))
      (node (ref "U19") (pin "3") (pinfunction "GND_3") (pintype "power_in"))
      (node (ref "U19") (pin "4") (pinfunction "GND_4") (pintype "power_in"))
      (node (ref "U19") (pin "6") (pinfunction "GND_6") (pintype "power_in"))
      (node (ref "U20") (pin "5") (pinfunction "VSS_5") (pintype "power_in"))
      (node (ref "U8") (pin "5") (pinfunction "VSS_5") (pintype "power_in"))
    )
    (net (code "49") (name "Net-(U12-SDO{slash}ADDR)") (class "Default")
      (node (ref "R29") (pin "2") (pinfunction "2_2") (pintype "passive"))
      (node (ref "U12") (pin "1") (pinfunction "SDO/ADDR_1") (pintype "passive"))
    )
    (net (code "50") (name "Net-(U13-SDO{slash}ADDR)") (class "Default")
      (node (ref "R30") (pin "2") (pinfunction "2_2") (pintype "passive"))
      (node (ref "U13") (pin "1") (pinfunction "SDO/ADDR_1") (pintype "passive"))
    )
    (net (code "51") (name "Net-(U15-SDO)") (class "Default")
      (node (ref "R31") (pin "2") (pinfunction "2_2") (pintype "passive"))
      (node (ref "U15") (pin "1") (pinfunction "SDO_1") (pintype "passive"))
    )
    (net (code "52") (name "Net-(U17-SDO{slash}ADDR)") (class "Default")
      (node (ref "R32") (pin "2") (pinfunction "2_2") (pintype "passive"))
      (node (ref "U17") (pin "1") (pinfunction "SDO/ADDR_1") (pintype "passive"))
    )
    (net (code "53") (name "Net-(U18-SDO{slash}ADDR)") (class "Default")
      (node (ref "R33") (pin "2") (pinfunction "2_2") (pintype "passive"))
      (node (ref "U18") (pin "1") (pinfunction "SDO/ADDR_1") (pintype "passive"))
    )
    (net (code "54") (name "unconnected-(U12-INT2-Pad6)") (class "Default")
      (node (ref "U12") (pin "6") (pinfunction "INT2_6") (pintype "passive+no_connect"))
    )
    (net (code "55") (name "unconnected-(U12-NC-Pad11)") (class "Default")
      (node (ref "U12") (pin "11") (pinfunction "NC_11") (pintype "passive+no_connect"))
    )
    (net (code "56") (name "unconnected-(U13-INT2-Pad6)") (class "Default")
      (node (ref "U13") (pin "6") (pinfunction "INT2_6") (pintype "passive+no_connect"))
    )
    (net (code "57") (name "unconnected-(U13-NC-Pad11)") (class "Default")
      (node (ref "U13") (pin "11") (pinfunction "NC_11") (pintype "passive+no_connect"))
    )
    (net (code "58") (name "unconnected-(U15-NC_1-Pad2)") (class "Default")
      (node (ref "U15") (pin "2") (pinfunction "NC_1_2") (pintype "passive+no_connect"))
    )
    (net (code "59") (name "unconnected-(U15-NC_2-Pad3)") (class "Default")
      (node (ref "U15") (pin "3") (pinfunction "NC_2_3") (pintype "passive+no_connect"))
    )
    (net (code "60") (name "unconnected-(U15-NC_3-Pad10)") (class "Default")
      (node (ref "U15") (pin "10") (pinfunction "NC_3_10") (pintype "passive+no_connect"))
    )
    (net (code "61") (name "unconnected-(U15-NC_4-Pad11)") (class "Default")
      (node (ref "U15") (pin "11") (pinfunction "NC_4_11") (pintype "passive+no_connect"))
    )
    (net (code "62") (name "unconnected-(U17-INT2-Pad6)") (class "Default")
      (node (ref "U17") (pin "6") (pinfunction "INT2_6") (pintype "passive+no_connect"))
    )
    (net (code "63") (name "unconnected-(U17-NC-Pad11)") (class "Default")
      (node (ref "U17") (pin "11") (pinfunction "NC_11") (pintype "passive+no_connect"))
    )
    (net (code "64") (name "unconnected-(U18-INT2-Pad6)") (class "Default")
      (node (ref "U18") (pin "6") (pinfunction "INT2_6") (pintype "passive+no_connect"))
    )
    (net (code "65") (name "unconnected-(U18-NC-Pad11)") (class "Default")
      (node (ref "U18") (pin "11") (pinfunction "NC_11") (pintype "passive+no_connect"))
    )
  )
)
